# LCDTFT_FPC40P_SPI3_3_2INCH_CTP.net
KiCad netlist of a schematic drawn in Altium Designer
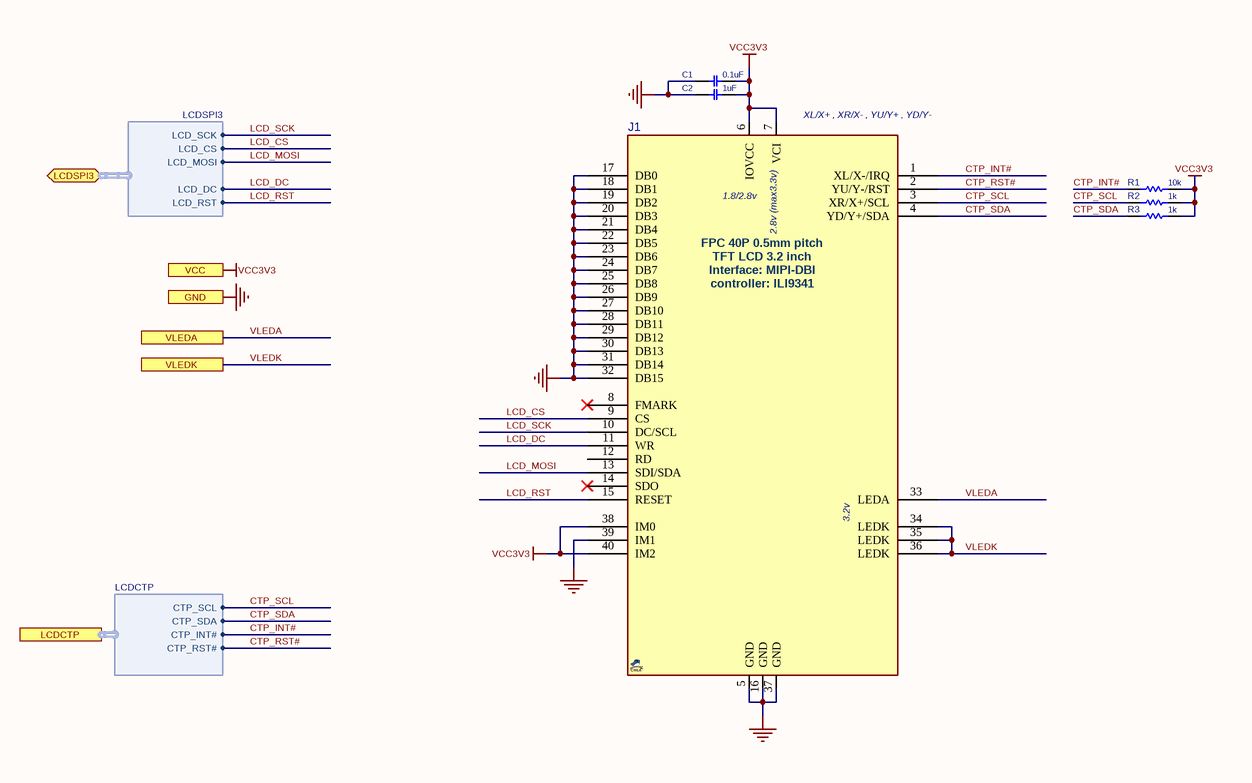
[diagram p0: LCDTFT_FPC40P_SPI3_3.2INCH_CTP.SchDoc]

(export (version "E")
  (design (tool "Eeschema 10.0.6"))
  (components
    (comp (ref "C1")
      (value "0.1uF")
      (footprint "C0402")
      (description "CAP, MLCC")
      (fields (field (name "MANF_P#") "GRM155R71H104KE14D") (field (name "MANF") "Murata"))
      (libsource (lib "passive_smd") (part "CAP_SMD_MLCC"))
    )
    (comp (ref "C2")
      (value "1uF")
      (footprint "C0402")
      (description "CAP, MLCC")
      (libsource (lib "passive_smd") (part "CAP_SMD_MLCC"))
    )
    (comp (ref "J1")
      (value "FPC50_40")
      (footprint "FPC50_40T")
      (description "LCD TFT Color, FPC40P, 3.2\" with touch")
      (fields (field (name "MANF") "Hirose") (field (name "MANF_P#") "FH12A-40S-0.5SH"))
      (libsource (lib "lcdtft") (part "LCDTFT_DBI_FPC40P_3.2INCH"))
    )
    (comp (ref "R1")
      (value "10k")
      (footprint "R0402")
      (description "RESISTOR, SMD")
      (libsource (lib "passive_res_smd") (part "RES_SMD"))
    )
    (comp (ref "R2")
      (value "1k")
      (footprint "R0402")
      (description "RESISTOR, SMD")
      (libsource (lib "passive_res_smd") (part "RES_SMD"))
    )
    (comp (ref "R3")
      (value "1k")
      (footprint "R0402")
      (description "RESISTOR, SMD")
      (libsource (lib "passive_res_smd") (part "RES_SMD"))
    )
  )
  (nets
    (net (code "3") (name "/CTP_INT#") (class "Default")
      (node (ref "J1") (pin "1") (pinfunction "XL/X-/IRQ_1") (pintype "passive"))
      (node (ref "R1") (pin "1") (pinfunction "1_1") (pintype "passive"))
    )
    (net (code "4") (name "/CTP_RST#") (class "Default")
      (node (ref "J1") (pin "2") (pinfunction "YU/Y-/RST_2") (pintype "passive"))
    )
    (net (code "5") (name "/CTP_SCL") (class "Default")
      (node (ref "J1") (pin "3") (pinfunction "XR/X+/SCL_3") (pintype "passive"))
      (node (ref "R2") (pin "1") (pinfunction "1_1") (pintype "passive"))
    )
    (net (code "6") (name "/CTP_SDA") (class "Default")
      (node (ref "J1") (pin "4") (pinfunction "YD/Y+/SDA_4") (pintype "passive"))
      (node (ref "R3") (pin "1") (pinfunction "1_1") (pintype "passive"))
    )
    (net (code "7") (name "/LCD_CS") (class "Default")
      (node (ref "J1") (pin "9") (pinfunction "CS_9") (pintype "passive"))
    )
    (net (code "8") (name "/LCD_DC") (class "Default")
      (node (ref "J1") (pin "11") (pinfunction "WR_11") (pintype "passive"))
    )
    (net (code "9") (name "/LCD_MOSI") (class "Default")
      (node (ref "J1") (pin "13") (pinfunction "SDI/SDA_13") (pintype "passive"))
    )
    (net (code "10") (name "/LCD_RST") (class "Default")
      (node (ref "J1") (pin "15") (pinfunction "RESET_15") (pintype "passive"))
    )
    (net (code "11") (name "/LCD_SCK") (class "Default")
      (node (ref "J1") (pin "10") (pinfunction "DC/SCL_10") (pintype "passive"))
    )
    (net (code "12") (name "/VLEDA") (class "Default")
      (node (ref "J1") (pin "33") (pinfunction "LEDA_33") (pintype "passive"))
    )
    (net (code "13") (name "/VLEDK") (class "Default")
      (node (ref "J1") (pin "34") (pinfunction "LEDK_34") (pintype "passive"))
      (node (ref "J1") (pin "35") (pinfunction "LEDK_35") (pintype "passive"))
      (node (ref "J1") (pin "36") (pinfunction "LEDK_36") (pintype "passive"))
    )
    (net (code "16") (name "GND") (class "Default")
      (node (ref "C1") (pin "2") (pinfunction "2_2") (pintype "passive"))
      (node (ref "C2") (pin "2") (pinfunction "2_2") (pintype "passive"))
      (node (ref "J1") (pin "16") (pinfunction "GND_16") (pintype "passive"))
      (node (ref "J1") (pin "17") (pinfunction "DB0_17") (pintype "passive"))
      (node (ref "J1") (pin "18") (pinfunction "DB1_18") (pintype "passive"))
      (node (ref "J1") (pin "19") (pinfunction "DB2_19") (pintype "passive"))
      (node (ref "J1") (pin "20") (pinfunction "DB3_20") (pintype "passive"))
      (node (ref "J1") (pin "21") (pinfunction "DB4_21") (pintype "passive"))
      (node (ref "J1") (pin "22") (pinfunction "DB5_22") (pintype "passive"))
      (node (ref "J1") (pin "23") (pinfunction "DB6_23") (pintype "passive"))
      (node (ref "J1") (pin "24") (pinfunction "DB7_24") (pintype "passive"))
      (node (ref "J1") (pin "25") (pinfunction "DB8_25") (pintype "passive"))
      (node (ref "J1") (pin "26") (pinfunction "DB9_26") (pintype "passive"))
      (node (ref "J1") (pin "27") (pinfunction "DB10_27") (pintype "passive"))
      (node (ref "J1") (pin "28") (pinfunction "DB11_28") (pintype "passive"))
      (node (ref "J1") (pin "29") (pinfunction "DB12_29") (pintype "passive"))
      (node (ref "J1") (pin "30") (pinfunction "DB13_30") (pintype "passive"))
      (node (ref "J1") (pin "31") (pinfunction "DB14_31") (pintype "passive"))
      (node (ref "J1") (pin "32") (pinfunction "DB15_32") (pintype "passive"))
      (node (ref "J1") (pin "37") (pinfunction "GND_37") (pintype "passive"))
      (node (ref "J1") (pin "39") (pinfunction "IM1_39") (pintype "passive"))
      (node (ref "J1") (pin "5") (pinfunction "GND_5") (pintype "passive"))
    )
    (net (code "17") (name "VCC3V3") (class "Default")
      (node (ref "C1") (pin "1") (pinfunction "1_1") (pintype "passive"))
      (node (ref "C2") (pin "1") (pinfunction "1_1") (pintype "passive"))
      (node (ref "J1") (pin "38") (pinfunction "IM0_38") (pintype "passive"))
      (node (ref "J1") (pin "40") (pinfunction "IM2_40") (pintype "passive"))
      (node (ref "J1") (pin "6") (pinfunction "IOVCC_6") (pintype "passive"))
      (node (ref "J1") (pin "7") (pinfunction "VCI_7") (pintype "passive"))
      (node (ref "R1") (pin "2") (pinfunction "2_2") (pintype "passive"))
      (node (ref "R2") (pin "2") (pinfunction "2_2") (pintype "passive"))
      (node (ref "R3") (pin "2") (pinfunction "2_2") (pintype "passive"))
    )
    (net (code "18") (name "unconnected-(J1-FMARK-Pad8)") (class "Default")
      (node (ref "J1") (pin "8") (pinfunction "FMARK_8") (pintype "passive+no_connect"))
    )
    (net (code "19") (name "unconnected-(J1-RD-Pad12)") (class "Default")
      (node (ref "J1") (pin "12") (pinfunction "RD_12") (pintype "passive"))
    )
    (net (code "20") (name "unconnected-(J1-SDO-Pad14)") (class "Default")
      (node (ref "J1") (pin "14") (pinfunction "SDO_14") (pintype "passive+no_connect"))
    )
  )
)
